# I2CHubMultiplexer.net
KiCad netlist of a schematic drawn in EAGLE
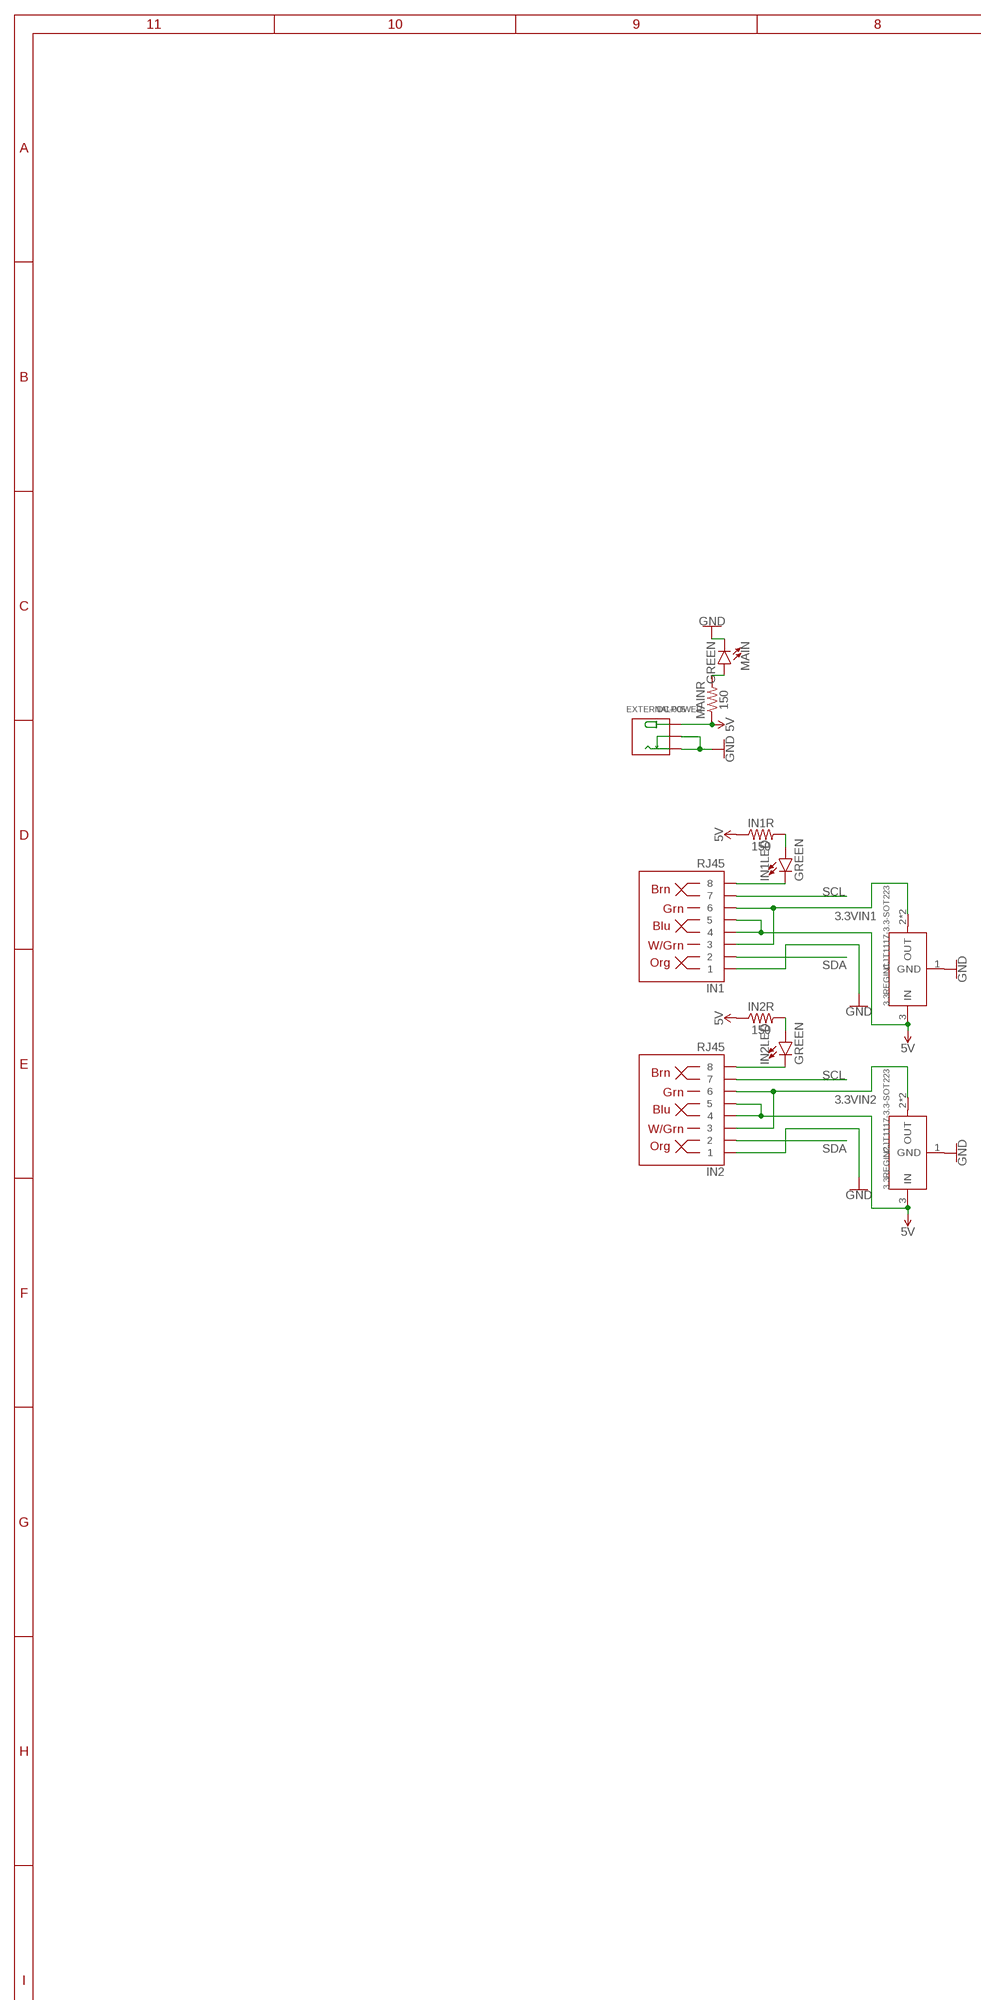
[diagram p0: schematic, sheet 1, part 1 of 2]
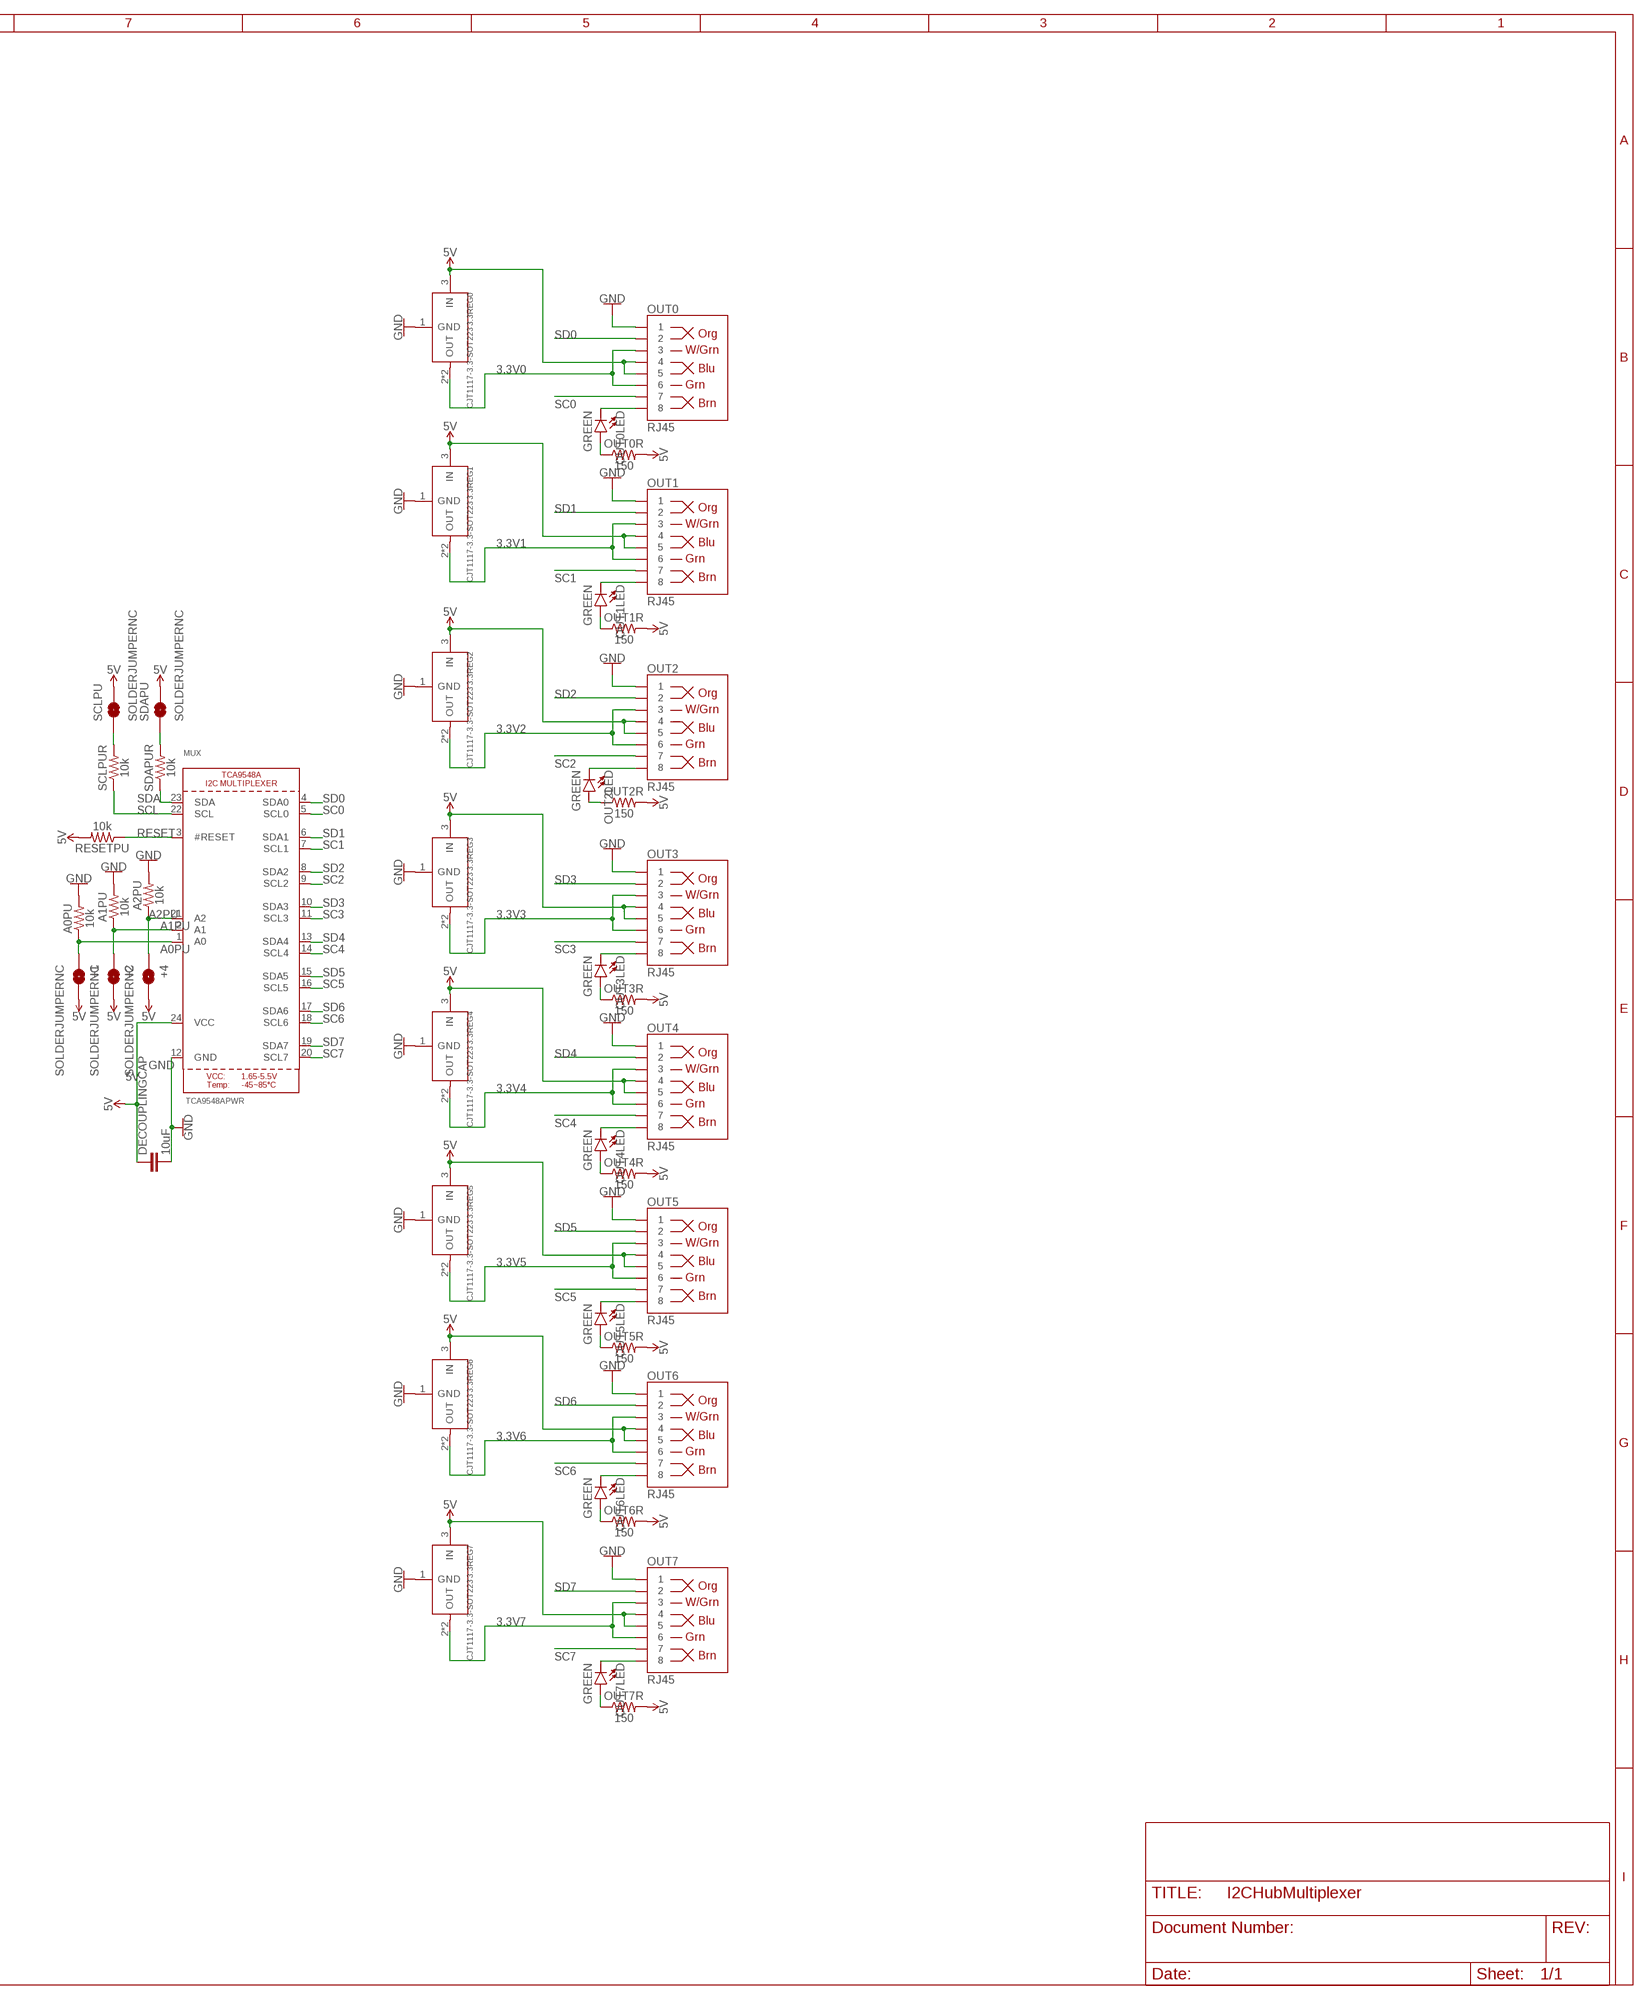
[diagram p1: schematic, sheet 1, part 2 of 2]

(export (version "E")
  (design (tool "Eeschema 10.0.6"))
  (components
    (comp (ref "+1")
      (value "SOLDERJUMPERNC")
      (footprint "eagle-import:SJ_2S")
      (libsource (lib "eagle-import") (part "SOLDERJUMPERNC"))
    )
    (comp (ref "+2")
      (value "SOLDERJUMPERNC")
      (footprint "eagle-import:SJ_2S")
      (libsource (lib "eagle-import") (part "SOLDERJUMPERNC"))
    )
    (comp (ref "+4")
      (value "SOLDERJUMPERNC")
      (footprint "eagle-import:SJ_2S")
      (libsource (lib "eagle-import") (part "SOLDERJUMPERNC"))
    )
    (comp (ref "3.3REG0")
      (value "CJT1117-3.3-SOT223")
      (footprint "eagle-import:SOT-223")
      (fields (field (name "MPN") "CJT1117-3.3"))
      (libsource (lib "eagle-import") (part "PMIC-CJT1117-3.3(SOT223)"))
    )
    (comp (ref "3.3REG1")
      (value "CJT1117-3.3-SOT223")
      (footprint "eagle-import:SOT-223")
      (fields (field (name "MPN") "CJT1117-3.3"))
      (libsource (lib "eagle-import") (part "PMIC-CJT1117-3.3(SOT223)"))
    )
    (comp (ref "3.3REG2")
      (value "CJT1117-3.3-SOT223")
      (footprint "eagle-import:SOT-223")
      (fields (field (name "MPN") "CJT1117-3.3"))
      (libsource (lib "eagle-import") (part "PMIC-CJT1117-3.3(SOT223)"))
    )
    (comp (ref "3.3REG3")
      (value "CJT1117-3.3-SOT223")
      (footprint "eagle-import:SOT-223")
      (fields (field (name "MPN") "CJT1117-3.3"))
      (libsource (lib "eagle-import") (part "PMIC-CJT1117-3.3(SOT223)"))
    )
    (comp (ref "3.3REG4")
      (value "CJT1117-3.3-SOT223")
      (footprint "eagle-import:SOT-223")
      (fields (field (name "MPN") "CJT1117-3.3"))
      (libsource (lib "eagle-import") (part "PMIC-CJT1117-3.3(SOT223)"))
    )
    (comp (ref "3.3REG5")
      (value "CJT1117-3.3-SOT223")
      (footprint "eagle-import:SOT-223")
      (fields (field (name "MPN") "CJT1117-3.3"))
      (libsource (lib "eagle-import") (part "PMIC-CJT1117-3.3(SOT223)"))
    )
    (comp (ref "3.3REG6")
      (value "CJT1117-3.3-SOT223")
      (footprint "eagle-import:SOT-223")
      (fields (field (name "MPN") "CJT1117-3.3"))
      (libsource (lib "eagle-import") (part "PMIC-CJT1117-3.3(SOT223)"))
    )
    (comp (ref "3.3REG7")
      (value "CJT1117-3.3-SOT223")
      (footprint "eagle-import:SOT-223")
      (fields (field (name "MPN") "CJT1117-3.3"))
      (libsource (lib "eagle-import") (part "PMIC-CJT1117-3.3(SOT223)"))
    )
    (comp (ref "3.3REGIN1")
      (value "CJT1117-3.3-SOT223")
      (footprint "eagle-import:SOT-223")
      (fields (field (name "MPN") "CJT1117-3.3"))
      (libsource (lib "eagle-import") (part "PMIC-CJT1117-3.3(SOT223)"))
    )
    (comp (ref "3.3REGIN2")
      (value "CJT1117-3.3-SOT223")
      (footprint "eagle-import:SOT-223")
      (fields (field (name "MPN") "CJT1117-3.3"))
      (libsource (lib "eagle-import") (part "PMIC-CJT1117-3.3(SOT223)"))
    )
    (comp (ref "A0PU")
      (value "10k")
      (footprint "eagle-import:0603")
      (libsource (lib "eagle-import") (part "10KOHM-0603-1/10W-1%"))
    )
    (comp (ref "A1PU")
      (value "10k")
      (footprint "eagle-import:0603")
      (libsource (lib "eagle-import") (part "10KOHM-0603-1/10W-1%"))
    )
    (comp (ref "A2PU")
      (value "10k")
      (footprint "eagle-import:0603")
      (libsource (lib "eagle-import") (part "10KOHM-0603-1/10W-1%"))
    )
    (comp (ref "DECOUPLINGCAP")
      (value "10uF")
      (footprint "eagle-import:0603")
      (libsource (lib "eagle-import") (part "10UF-0603-6.3V-20%"))
    )
    (comp (ref "EXTERNALPOWER")
      (value "DC-005")
      (footprint "eagle-import:DCJ3P-14.2X11.0X9.0MM")
      (libsource (lib "eagle-import") (part "CONN-POWER-JACK-2.1MM(DC-005)"))
    )
    (comp (ref "IN1")
      (value "RJ45")
      (footprint "eagle-import:RJ45-8")
      (libsource (lib "eagle-import") (part "RJ45-8"))
    )
    (comp (ref "IN1LED")
      (value "GREEN")
      (footprint "eagle-import:LED-0603")
      (libsource (lib "eagle-import") (part "LED-GREEN0603"))
    )
    (comp (ref "IN1R")
      (value "150")
      (footprint "eagle-import:0603")
      (libsource (lib "eagle-import") (part "150OHM-0603-1/10W-1%"))
    )
    (comp (ref "IN2")
      (value "RJ45")
      (footprint "eagle-import:RJ45-8")
      (libsource (lib "eagle-import") (part "RJ45-8"))
    )
    (comp (ref "IN2LED")
      (value "GREEN")
      (footprint "eagle-import:LED-0603")
      (libsource (lib "eagle-import") (part "LED-GREEN0603"))
    )
    (comp (ref "IN2R")
      (value "150")
      (footprint "eagle-import:0603")
      (libsource (lib "eagle-import") (part "150OHM-0603-1/10W-1%"))
    )
    (comp (ref "MAIN")
      (value "GREEN")
      (footprint "eagle-import:LED-0603")
      (libsource (lib "eagle-import") (part "LED-GREEN0603"))
    )
    (comp (ref "MAINR")
      (value "150")
      (footprint "eagle-import:0603")
      (libsource (lib "eagle-import") (part "150OHM-0603-1/10W-1%"))
    )
    (comp (ref "MUX")
      (value "TCA9548APWR")
      (footprint "eagle-import:TSSOP24")
      (libsource (lib "eagle-import") (part "TCA9548A"))
    )
    (comp (ref "OUT0")
      (value "RJ45")
      (footprint "eagle-import:RJ45-8")
      (libsource (lib "eagle-import") (part "RJ45-8"))
    )
    (comp (ref "OUT0LED")
      (value "GREEN")
      (footprint "eagle-import:LED-0603")
      (libsource (lib "eagle-import") (part "LED-GREEN0603"))
    )
    (comp (ref "OUT0R")
      (value "150")
      (footprint "eagle-import:0603")
      (libsource (lib "eagle-import") (part "150OHM-0603-1/10W-1%"))
    )
    (comp (ref "OUT1")
      (value "RJ45")
      (footprint "eagle-import:RJ45-8")
      (libsource (lib "eagle-import") (part "RJ45-8"))
    )
    (comp (ref "OUT1LED")
      (value "GREEN")
      (footprint "eagle-import:LED-0603")
      (libsource (lib "eagle-import") (part "LED-GREEN0603"))
    )
    (comp (ref "OUT1R")
      (value "150")
      (footprint "eagle-import:0603")
      (libsource (lib "eagle-import") (part "150OHM-0603-1/10W-1%"))
    )
    (comp (ref "OUT2")
      (value "RJ45")
      (footprint "eagle-import:RJ45-8")
      (libsource (lib "eagle-import") (part "RJ45-8"))
    )
    (comp (ref "OUT2LED")
      (value "GREEN")
      (footprint "eagle-import:LED-0603")
      (libsource (lib "eagle-import") (part "LED-GREEN0603"))
    )
    (comp (ref "OUT2R")
      (value "150")
      (footprint "eagle-import:0603")
      (libsource (lib "eagle-import") (part "150OHM-0603-1/10W-1%"))
    )
    (comp (ref "OUT3")
      (value "RJ45")
      (footprint "eagle-import:RJ45-8")
      (libsource (lib "eagle-import") (part "RJ45-8"))
    )
    (comp (ref "OUT3LED")
      (value "GREEN")
      (footprint "eagle-import:LED-0603")
      (libsource (lib "eagle-import") (part "LED-GREEN0603"))
    )
    (comp (ref "OUT3R")
      (value "150")
      (footprint "eagle-import:0603")
      (libsource (lib "eagle-import") (part "150OHM-0603-1/10W-1%"))
    )
    (comp (ref "OUT4")
      (value "RJ45")
      (footprint "eagle-import:RJ45-8")
      (libsource (lib "eagle-import") (part "RJ45-8"))
    )
    (comp (ref "OUT4LED")
      (value "GREEN")
      (footprint "eagle-import:LED-0603")
      (libsource (lib "eagle-import") (part "LED-GREEN0603"))
    )
    (comp (ref "OUT4R")
      (value "150")
      (footprint "eagle-import:0603")
      (libsource (lib "eagle-import") (part "150OHM-0603-1/10W-1%"))
    )
    (comp (ref "OUT5")
      (value "RJ45")
      (footprint "eagle-import:RJ45-8")
      (libsource (lib "eagle-import") (part "RJ45-8"))
    )
    (comp (ref "OUT5LED")
      (value "GREEN")
      (footprint "eagle-import:LED-0603")
      (libsource (lib "eagle-import") (part "LED-GREEN0603"))
    )
    (comp (ref "OUT5R")
      (value "150")
      (footprint "eagle-import:0603")
      (libsource (lib "eagle-import") (part "150OHM-0603-1/10W-1%"))
    )
    (comp (ref "OUT6")
      (value "RJ45")
      (footprint "eagle-import:RJ45-8")
      (libsource (lib "eagle-import") (part "RJ45-8"))
    )
    (comp (ref "OUT6LED")
      (value "GREEN")
      (footprint "eagle-import:LED-0603")
      (libsource (lib "eagle-import") (part "LED-GREEN0603"))
    )
    (comp (ref "OUT6R")
      (value "150")
      (footprint "eagle-import:0603")
      (libsource (lib "eagle-import") (part "150OHM-0603-1/10W-1%"))
    )
    (comp (ref "OUT7")
      (value "RJ45")
      (footprint "eagle-import:RJ45-8")
      (libsource (lib "eagle-import") (part "RJ45-8"))
    )
    (comp (ref "OUT7LED")
      (value "GREEN")
      (footprint "eagle-import:LED-0603")
      (libsource (lib "eagle-import") (part "LED-GREEN0603"))
    )
    (comp (ref "OUT7R")
      (value "150")
      (footprint "eagle-import:0603")
      (libsource (lib "eagle-import") (part "150OHM-0603-1/10W-1%"))
    )
    (comp (ref "RESETPU")
      (value "10k")
      (footprint "eagle-import:0603")
      (libsource (lib "eagle-import") (part "10KOHM-0603-1/10W-1%"))
    )
    (comp (ref "SCLPU")
      (value "SOLDERJUMPERNC")
      (footprint "eagle-import:SJ_2S")
      (libsource (lib "eagle-import") (part "SOLDERJUMPERNC"))
    )
    (comp (ref "SCLPUR")
      (value "10k")
      (footprint "eagle-import:0603")
      (libsource (lib "eagle-import") (part "10KOHM-0603-1/10W-1%"))
    )
    (comp (ref "SDAPU")
      (value "SOLDERJUMPERNC")
      (footprint "eagle-import:SJ_2S")
      (libsource (lib "eagle-import") (part "SOLDERJUMPERNC"))
    )
    (comp (ref "SDAPUR")
      (value "10k")
      (footprint "eagle-import:0603")
      (libsource (lib "eagle-import") (part "10KOHM-0603-1/10W-1%"))
    )
  )
  (nets
    (net (code "1") (name "/3.3V0") (class "Default")
      (node (ref "3.3REG0") (pin "2") (pinfunction "OUT_2") (pintype "bidirectional"))
      (node (ref "3.3REG0") (pin "TER") (pinfunction "OUT_TER") (pintype "bidirectional"))
      (node (ref "OUT0") (pin "3") (pinfunction "3_3") (pintype "bidirectional"))
      (node (ref "OUT0") (pin "6") (pinfunction "6_6") (pintype "bidirectional"))
    )
    (net (code "2") (name "/3.3V1") (class "Default")
      (node (ref "3.3REG1") (pin "2") (pinfunction "OUT_2") (pintype "bidirectional"))
      (node (ref "3.3REG1") (pin "TER") (pinfunction "OUT_TER") (pintype "bidirectional"))
      (node (ref "OUT1") (pin "3") (pinfunction "3_3") (pintype "bidirectional"))
      (node (ref "OUT1") (pin "6") (pinfunction "6_6") (pintype "bidirectional"))
    )
    (net (code "3") (name "/3.3V2") (class "Default")
      (node (ref "3.3REG2") (pin "2") (pinfunction "OUT_2") (pintype "bidirectional"))
      (node (ref "3.3REG2") (pin "TER") (pinfunction "OUT_TER") (pintype "bidirectional"))
      (node (ref "OUT2") (pin "3") (pinfunction "3_3") (pintype "bidirectional"))
      (node (ref "OUT2") (pin "6") (pinfunction "6_6") (pintype "bidirectional"))
    )
    (net (code "4") (name "/3.3V3") (class "Default")
      (node (ref "3.3REG3") (pin "2") (pinfunction "OUT_2") (pintype "bidirectional"))
      (node (ref "3.3REG3") (pin "TER") (pinfunction "OUT_TER") (pintype "bidirectional"))
      (node (ref "OUT3") (pin "3") (pinfunction "3_3") (pintype "bidirectional"))
      (node (ref "OUT3") (pin "6") (pinfunction "6_6") (pintype "bidirectional"))
    )
    (net (code "5") (name "/3.3V4") (class "Default")
      (node (ref "3.3REG4") (pin "2") (pinfunction "OUT_2") (pintype "bidirectional"))
      (node (ref "3.3REG4") (pin "TER") (pinfunction "OUT_TER") (pintype "bidirectional"))
      (node (ref "OUT4") (pin "3") (pinfunction "3_3") (pintype "bidirectional"))
      (node (ref "OUT4") (pin "6") (pinfunction "6_6") (pintype "bidirectional"))
    )
    (net (code "6") (name "/3.3V5") (class "Default")
      (node (ref "3.3REG5") (pin "2") (pinfunction "OUT_2") (pintype "bidirectional"))
      (node (ref "3.3REG5") (pin "TER") (pinfunction "OUT_TER") (pintype "bidirectional"))
      (node (ref "OUT5") (pin "3") (pinfunction "3_3") (pintype "bidirectional"))
      (node (ref "OUT5") (pin "6") (pinfunction "6_6") (pintype "bidirectional"))
    )
    (net (code "7") (name "/3.3V6") (class "Default")
      (node (ref "3.3REG6") (pin "2") (pinfunction "OUT_2") (pintype "bidirectional"))
      (node (ref "3.3REG6") (pin "TER") (pinfunction "OUT_TER") (pintype "bidirectional"))
      (node (ref "OUT6") (pin "3") (pinfunction "3_3") (pintype "bidirectional"))
      (node (ref "OUT6") (pin "6") (pinfunction "6_6") (pintype "bidirectional"))
    )
    (net (code "8") (name "/3.3V7") (class "Default")
      (node (ref "3.3REG7") (pin "2") (pinfunction "OUT_2") (pintype "bidirectional"))
      (node (ref "3.3REG7") (pin "TER") (pinfunction "OUT_TER") (pintype "bidirectional"))
      (node (ref "OUT7") (pin "3") (pinfunction "3_3") (pintype "bidirectional"))
      (node (ref "OUT7") (pin "6") (pinfunction "6_6") (pintype "bidirectional"))
    )
    (net (code "9") (name "/3.3VIN1") (class "Default")
      (node (ref "3.3REGIN1") (pin "2") (pinfunction "OUT_2") (pintype "bidirectional"))
      (node (ref "3.3REGIN1") (pin "TER") (pinfunction "OUT_TER") (pintype "bidirectional"))
      (node (ref "IN1") (pin "3") (pinfunction "3_3") (pintype "bidirectional"))
      (node (ref "IN1") (pin "6") (pinfunction "6_6") (pintype "bidirectional"))
    )
    (net (code "10") (name "/3.3VIN2") (class "Default")
      (node (ref "3.3REGIN2") (pin "2") (pinfunction "OUT_2") (pintype "bidirectional"))
      (node (ref "3.3REGIN2") (pin "TER") (pinfunction "OUT_TER") (pintype "bidirectional"))
      (node (ref "IN2") (pin "3") (pinfunction "3_3") (pintype "bidirectional"))
      (node (ref "IN2") (pin "6") (pinfunction "6_6") (pintype "bidirectional"))
    )
    (net (code "11") (name "/A0PU") (class "Default")
      (node (ref "+1") (pin "1") (pinfunction "1_1") (pintype "passive"))
      (node (ref "A0PU") (pin "1") (pinfunction "1_1") (pintype "passive"))
      (node (ref "MUX") (pin "1") (pinfunction "A0_1") (pintype "bidirectional"))
    )
    (net (code "12") (name "/A1PU") (class "Default")
      (node (ref "+2") (pin "1") (pinfunction "1_1") (pintype "passive"))
      (node (ref "A1PU") (pin "1") (pinfunction "1_1") (pintype "passive"))
      (node (ref "MUX") (pin "2") (pinfunction "A1_2") (pintype "bidirectional"))
    )
    (net (code "13") (name "/A2PU") (class "Default")
      (node (ref "+4") (pin "1") (pinfunction "1_1") (pintype "passive"))
      (node (ref "A2PU") (pin "1") (pinfunction "1_1") (pintype "passive"))
      (node (ref "MUX") (pin "21") (pinfunction "A2_21") (pintype "bidirectional"))
    )
    (net (code "14") (name "/RESET") (class "Default")
      (node (ref "MUX") (pin "3") (pinfunction "#RESET_3") (pintype "bidirectional"))
      (node (ref "RESETPU") (pin "1") (pinfunction "1_1") (pintype "passive"))
    )
    (net (code "15") (name "/SC0") (class "Default")
      (node (ref "MUX") (pin "5") (pinfunction "SCL0_5") (pintype "bidirectional"))
      (node (ref "OUT0") (pin "7") (pinfunction "7_7") (pintype "bidirectional"))
    )
    (net (code "16") (name "/SC1") (class "Default")
      (node (ref "MUX") (pin "7") (pinfunction "SCL1_7") (pintype "bidirectional"))
      (node (ref "OUT1") (pin "7") (pinfunction "7_7") (pintype "bidirectional"))
    )
    (net (code "17") (name "/SC2") (class "Default")
      (node (ref "MUX") (pin "9") (pinfunction "SCL2_9") (pintype "bidirectional"))
      (node (ref "OUT2") (pin "7") (pinfunction "7_7") (pintype "bidirectional"))
    )
    (net (code "18") (name "/SC3") (class "Default")
      (node (ref "MUX") (pin "11") (pinfunction "SCL3_11") (pintype "bidirectional"))
      (node (ref "OUT3") (pin "7") (pinfunction "7_7") (pintype "bidirectional"))
    )
    (net (code "19") (name "/SC4") (class "Default")
      (node (ref "MUX") (pin "14") (pinfunction "SCL4_14") (pintype "bidirectional"))
      (node (ref "OUT4") (pin "7") (pinfunction "7_7") (pintype "bidirectional"))
    )
    (net (code "20") (name "/SC5") (class "Default")
      (node (ref "MUX") (pin "16") (pinfunction "SCL5_16") (pintype "bidirectional"))
      (node (ref "OUT5") (pin "7") (pinfunction "7_7") (pintype "bidirectional"))
    )
    (net (code "21") (name "/SC6") (class "Default")
      (node (ref "MUX") (pin "18") (pinfunction "SCL6_18") (pintype "bidirectional"))
      (node (ref "OUT6") (pin "7") (pinfunction "7_7") (pintype "bidirectional"))
    )
    (net (code "22") (name "/SC7") (class "Default")
      (node (ref "MUX") (pin "20") (pinfunction "SCL7_20") (pintype "bidirectional"))
      (node (ref "OUT7") (pin "7") (pinfunction "7_7") (pintype "bidirectional"))
    )
    (net (code "23") (name "/SCL") (class "Default")
      (node (ref "IN1") (pin "7") (pinfunction "7_7") (pintype "bidirectional"))
      (node (ref "IN2") (pin "7") (pinfunction "7_7") (pintype "bidirectional"))
      (node (ref "MUX") (pin "22") (pinfunction "SCL_22") (pintype "bidirectional"))
      (node (ref "SCLPUR") (pin "1") (pinfunction "1_1") (pintype "passive"))
    )
    (net (code "24") (name "/SD0") (class "Default")
      (node (ref "MUX") (pin "4") (pinfunction "SDA0_4") (pintype "bidirectional"))
      (node (ref "OUT0") (pin "2") (pinfunction "2_2") (pintype "bidirectional"))
    )
    (net (code "25") (name "/SD1") (class "Default")
      (node (ref "MUX") (pin "6") (pinfunction "SDA1_6") (pintype "bidirectional"))
      (node (ref "OUT1") (pin "2") (pinfunction "2_2") (pintype "bidirectional"))
    )
    (net (code "26") (name "/SD2") (class "Default")
      (node (ref "MUX") (pin "8") (pinfunction "SDA2_8") (pintype "bidirectional"))
      (node (ref "OUT2") (pin "2") (pinfunction "2_2") (pintype "bidirectional"))
    )
    (net (code "27") (name "/SD3") (class "Default")
      (node (ref "MUX") (pin "10") (pinfunction "SDA3_10") (pintype "bidirectional"))
      (node (ref "OUT3") (pin "2") (pinfunction "2_2") (pintype "bidirectional"))
    )
    (net (code "28") (name "/SD4") (class "Default")
      (node (ref "MUX") (pin "13") (pinfunction "SDA4_13") (pintype "bidirectional"))
      (node (ref "OUT4") (pin "2") (pinfunction "2_2") (pintype "bidirectional"))
    )
    (net (code "29") (name "/SD5") (class "Default")
      (node (ref "MUX") (pin "15") (pinfunction "SDA5_15") (pintype "bidirectional"))
      (node (ref "OUT5") (pin "2") (pinfunction "2_2") (pintype "bidirectional"))
    )
    (net (code "30") (name "/SD6") (class "Default")
      (node (ref "MUX") (pin "17") (pinfunction "SDA6_17") (pintype "bidirectional"))
      (node (ref "OUT6") (pin "2") (pinfunction "2_2") (pintype "bidirectional"))
    )
    (net (code "31") (name "/SD7") (class "Default")
      (node (ref "MUX") (pin "19") (pinfunction "SDA7_19") (pintype "bidirectional"))
      (node (ref "OUT7") (pin "2") (pinfunction "2_2") (pintype "bidirectional"))
    )
    (net (code "32") (name "/SDA") (class "Default")
      (node (ref "IN1") (pin "2") (pinfunction "2_2") (pintype "bidirectional"))
      (node (ref "IN2") (pin "2") (pinfunction "2_2") (pintype "bidirectional"))
      (node (ref "MUX") (pin "23") (pinfunction "SDA_23") (pintype "bidirectional"))
      (node (ref "SDAPUR") (pin "1") (pinfunction "1_1") (pintype "passive"))
    )
    (net (code "33") (name "5V") (class "Default")
      (node (ref "+1") (pin "2") (pinfunction "2_2") (pintype "passive"))
      (node (ref "+2") (pin "2") (pinfunction "2_2") (pintype "passive"))
      (node (ref "+4") (pin "2") (pinfunction "2_2") (pintype "passive"))
      (node (ref "3.3REG0") (pin "3") (pinfunction "IN_3") (pintype "bidirectional"))
      (node (ref "3.3REG1") (pin "3") (pinfunction "IN_3") (pintype "bidirectional"))
      (node (ref "3.3REG2") (pin "3") (pinfunction "IN_3") (pintype "bidirectional"))
      (node (ref "3.3REG3") (pin "3") (pinfunction "IN_3") (pintype "bidirectional"))
      (node (ref "3.3REG4") (pin "3") (pinfunction "IN_3") (pintype "bidirectional"))
      (node (ref "3.3REG5") (pin "3") (pinfunction "IN_3") (pintype "bidirectional"))
      (node (ref "3.3REG6") (pin "3") (pinfunction "IN_3") (pintype "bidirectional"))
      (node (ref "3.3REG7") (pin "3") (pinfunction "IN_3") (pintype "bidirectional"))
      (node (ref "3.3REGIN1") (pin "3") (pinfunction "IN_3") (pintype "bidirectional"))
      (node (ref "3.3REGIN2") (pin "3") (pinfunction "IN_3") (pintype "bidirectional"))
      (node (ref "DECOUPLINGCAP") (pin "1") (pinfunction "1_1") (pintype "passive"))
      (node (ref "EXTERNALPOWER") (pin "+") (pinfunction "+_+") (pintype "bidirectional"))
      (node (ref "IN1") (pin "4") (pinfunction "4_4") (pintype "bidirectional"))
      (node (ref "IN1") (pin "5") (pinfunction "5_5") (pintype "bidirectional"))
      (node (ref "IN1R") (pin "1") (pinfunction "1_1") (pintype "passive"))
      (node (ref "IN2") (pin "4") (pinfunction "4_4") (pintype "bidirectional"))
      (node (ref "IN2") (pin "5") (pinfunction "5_5") (pintype "bidirectional"))
      (node (ref "IN2R") (pin "1") (pinfunction "1_1") (pintype "passive"))
      (node (ref "MAINR") (pin "1") (pinfunction "1_1") (pintype "passive"))
      (node (ref "MUX") (pin "24") (pinfunction "VCC_24") (pintype "bidirectional"))
      (node (ref "OUT0") (pin "4") (pinfunction "4_4") (pintype "bidirectional"))
      (node (ref "OUT0") (pin "5") (pinfunction "5_5") (pintype "bidirectional"))
      (node (ref "OUT0R") (pin "2") (pinfunction "2_2") (pintype "passive"))
      (node (ref "OUT1") (pin "4") (pinfunction "4_4") (pintype "bidirectional"))
      (node (ref "OUT1") (pin "5") (pinfunction "5_5") (pintype "bidirectional"))
      (node (ref "OUT1R") (pin "2") (pinfunction "2_2") (pintype "passive"))
      (node (ref "OUT2") (pin "4") (pinfunction "4_4") (pintype "bidirectional"))
      (node (ref "OUT2") (pin "5") (pinfunction "5_5") (pintype "bidirectional"))
      (node (ref "OUT2R") (pin "2") (pinfunction "2_2") (pintype "passive"))
      (node (ref "OUT3") (pin "4") (pinfunction "4_4") (pintype "bidirectional"))
      (node (ref "OUT3") (pin "5") (pinfunction "5_5") (pintype "bidirectional"))
      (node (ref "OUT3R") (pin "2") (pinfunction "2_2") (pintype "passive"))
      (node (ref "OUT4") (pin "4") (pinfunction "4_4") (pintype "bidirectional"))
      (node (ref "OUT4") (pin "5") (pinfunction "5_5") (pintype "bidirectional"))
      (node (ref "OUT4R") (pin "2") (pinfunction "2_2") (pintype "passive"))
      (node (ref "OUT5") (pin "4") (pinfunction "4_4") (pintype "bidirectional"))
      (node (ref "OUT5") (pin "5") (pinfunction "5_5") (pintype "bidirectional"))
      (node (ref "OUT5R") (pin "2") (pinfunction "2_2") (pintype "passive"))
      (node (ref "OUT6") (pin "4") (pinfunction "4_4") (pintype "bidirectional"))
      (node (ref "OUT6") (pin "5") (pinfunction "5_5") (pintype "bidirectional"))
      (node (ref "OUT6R") (pin "2") (pinfunction "2_2") (pintype "passive"))
      (node (ref "OUT7") (pin "4") (pinfunction "4_4") (pintype "bidirectional"))
      (node (ref "OUT7") (pin "5") (pinfunction "5_5") (pintype "bidirectional"))
      (node (ref "OUT7R") (pin "2") (pinfunction "2_2") (pintype "passive"))
      (node (ref "RESETPU") (pin "2") (pinfunction "2_2") (pintype "passive"))
      (node (ref "SCLPU") (pin "2") (pinfunction "2_2") (pintype "passive"))
      (node (ref "SDAPU") (pin "2") (pinfunction "2_2") (pintype "passive"))
    )
    (net (code "34") (name "GND") (class "Default")
      (node (ref "3.3REG0") (pin "1") (pinfunction "GND_1") (pintype "bidirectional"))
      (node (ref "3.3REG1") (pin "1") (pinfunction "GND_1") (pintype "bidirectional"))
      (node (ref "3.3REG2") (pin "1") (pinfunction "GND_1") (pintype "bidirectional"))
      (node (ref "3.3REG3") (pin "1") (pinfunction "GND_1") (pintype "bidirectional"))
      (node (ref "3.3REG4") (pin "1") (pinfunction "GND_1") (pintype "bidirectional"))
      (node (ref "3.3REG5") (pin "1") (pinfunction "GND_1") (pintype "bidirectional"))
      (node (ref "3.3REG6") (pin "1") (pinfunction "GND_1") (pintype "bidirectional"))
      (node (ref "3.3REG7") (pin "1") (pinfunction "GND_1") (pintype "bidirectional"))
      (node (ref "3.3REGIN1") (pin "1") (pinfunction "GND_1") (pintype "bidirectional"))
      (node (ref "3.3REGIN2") (pin "1") (pinfunction "GND_1") (pintype "bidirectional"))
      (node (ref "A0PU") (pin "2") (pinfunction "2_2") (pintype "passive"))
      (node (ref "A1PU") (pin "2") (pinfunction "2_2") (pintype "passive"))
      (node (ref "A2PU") (pin "2") (pinfunction "2_2") (pintype "passive"))
      (node (ref "DECOUPLINGCAP") (pin "2") (pinfunction "2_2") (pintype "passive"))
      (node (ref "EXTERNALPOWER") (pin "-1") (pinfunction "-_-1") (pintype "bidirectional"))
      (node (ref "EXTERNALPOWER") (pin "-2") (pinfunction "CDN_-2") (pintype "bidirectional"))
      (node (ref "IN1") (pin "1") (pinfunction "1_1") (pintype "bidirectional"))
      (node (ref "IN2") (pin "1") (pinfunction "1_1") (pintype "bidirectional"))
      (node (ref "MAIN") (pin "C") (pinfunction "C_C") (pintype "passive"))
      (node (ref "MUX") (pin "12") (pinfunction "GND_12") (pintype "bidirectional"))
      (node (ref "OUT0") (pin "1") (pinfunction "1_1") (pintype "bidirectional"))
      (node (ref "OUT1") (pin "1") (pinfunction "1_1") (pintype "bidirectional"))
      (node (ref "OUT2") (pin "1") (pinfunction "1_1") (pintype "bidirectional"))
      (node (ref "OUT3") (pin "1") (pinfunction "1_1") (pintype "bidirectional"))
      (node (ref "OUT4") (pin "1") (pinfunction "1_1") (pintype "bidirectional"))
      (node (ref "OUT5") (pin "1") (pinfunction "1_1") (pintype "bidirectional"))
      (node (ref "OUT6") (pin "1") (pinfunction "1_1") (pintype "bidirectional"))
      (node (ref "OUT7") (pin "1") (pinfunction "1_1") (pintype "bidirectional"))
    )
    (net (code "35") (name "Net-(IN1-Pad8)") (class "Default")
      (node (ref "IN1") (pin "8") (pinfunction "8_8") (pintype "bidirectional"))
      (node (ref "IN1LED") (pin "C") (pinfunction "C_C") (pintype "passive"))
    )
    (net (code "36") (name "Net-(IN1LED-PadA)") (class "Default")
      (node (ref "IN1LED") (pin "A") (pinfunction "A_A") (pintype "passive"))
      (node (ref "IN1R") (pin "2") (pinfunction "2_2") (pintype "passive"))
    )
    (net (code "37") (name "Net-(IN2-Pad8)") (class "Default")
      (node (ref "IN2") (pin "8") (pinfunction "8_8") (pintype "bidirectional"))
      (node (ref "IN2LED") (pin "C") (pinfunction "C_C") (pintype "passive"))
    )
    (net (code "38") (name "Net-(IN2LED-PadA)") (class "Default")
      (node (ref "IN2LED") (pin "A") (pinfunction "A_A") (pintype "passive"))
      (node (ref "IN2R") (pin "2") (pinfunction "2_2") (pintype "passive"))
    )
    (net (code "39") (name "Net-(MAIN-PadA)") (class "Default")
      (node (ref "MAIN") (pin "A") (pinfunction "A_A") (pintype "passive"))
      (node (ref "MAINR") (pin "2") (pinfunction "2_2") (pintype "passive"))
    )
    (net (code "40") (name "Net-(OUT0-Pad8)") (class "Default")
      (node (ref "OUT0") (pin "8") (pinfunction "8_8") (pintype "bidirectional"))
      (node (ref "OUT0LED") (pin "C") (pinfunction "C_C") (pintype "passive"))
    )
    (net (code "41") (name "Net-(OUT0LED-PadA)") (class "Default")
      (node (ref "OUT0LED") (pin "A") (pinfunction "A_A") (pintype "passive"))
      (node (ref "OUT0R") (pin "1") (pinfunction "1_1") (pintype "passive"))
    )
    (net (code "42") (name "Net-(OUT1-Pad8)") (class "Default")
      (node (ref "OUT1") (pin "8") (pinfunction "8_8") (pintype "bidirectional"))
      (node (ref "OUT1LED") (pin "C") (pinfunction "C_C") (pintype "passive"))
    )
    (net (code "43") (name "Net-(OUT1LED-PadA)") (class "Default")
      (node (ref "OUT1LED") (pin "A") (pinfunction "A_A") (pintype "passive"))
      (node (ref "OUT1R") (pin "1") (pinfunction "1_1") (pintype "passive"))
    )
    (net (code "44") (name "Net-(OUT2-Pad8)") (class "Default")
      (node (ref "OUT2") (pin "8") (pinfunction "8_8") (pintype "bidirectional"))
      (node (ref "OUT2LED") (pin "C") (pinfunction "C_C") (pintype "passive"))
    )
    (net (code "45") (name "Net-(OUT2LED-PadA)") (class "Default")
      (node (ref "OUT2LED") (pin "A") (pinfunction "A_A") (pintype "passive"))
      (node (ref "OUT2R") (pin "1") (pinfunction "1_1") (pintype "passive"))
    )
    (net (code "46") (name "Net-(OUT3-Pad8)") (class "Default")
      (node (ref "OUT3") (pin "8") (pinfunction "8_8") (pintype "bidirectional"))
      (node (ref "OUT3LED") (pin "C") (pinfunction "C_C") (pintype "passive"))
    )
    (net (code "47") (name "Net-(OUT3LED-PadA)") (class "Default")
      (node (ref "OUT3LED") (pin "A") (pinfunction "A_A") (pintype "passive"))
      (node (ref "OUT3R") (pin "1") (pinfunction "1_1") (pintype "passive"))
    )
    (net (code "48") (name "Net-(OUT4-Pad8)") (class "Default")
      (node (ref "OUT4") (pin "8") (pinfunction "8_8") (pintype "bidirectional"))
      (node (ref "OUT4LED") (pin "C") (pinfunction "C_C") (pintype "passive"))
    )
    (net (code "49") (name "Net-(OUT4LED-PadA)") (class "Default")
      (node (ref "OUT4LED") (pin "A") (pinfunction "A_A") (pintype "passive"))
      (node (ref "OUT4R") (pin "1") (pinfunction "1_1") (pintype "passive"))
    )
    (net (code "50") (name "Net-(OUT5-Pad8)") (class "Default")
      (node (ref "OUT5") (pin "8") (pinfunction "8_8") (pintype "bidirectional"))
      (node (ref "OUT5LED") (pin "C") (pinfunction "C_C") (pintype "passive"))
    )
    (net (code "51") (name "Net-(OUT5LED-PadA)") (class "Default")
      (node (ref "OUT5LED") (pin "A") (pinfunction "A_A") (pintype "passive"))
      (node (ref "OUT5R") (pin "1") (pinfunction "1_1") (pintype "passive"))
    )
    (net (code "52") (name "Net-(OUT6-Pad8)") (class "Default")
      (node (ref "OUT6") (pin "8") (pinfunction "8_8") (pintype "bidirectional"))
      (node (ref "OUT6LED") (pin "C") (pinfunction "C_C") (pintype "passive"))
    )
    (net (code "53") (name "Net-(OUT6LED-PadA)") (class "Default")
      (node (ref "OUT6LED") (pin "A") (pinfunction "A_A") (pintype "passive"))
      (node (ref "OUT6R") (pin "1") (pinfunction "1_1") (pintype "passive"))
    )
    (net (code "54") (name "Net-(OUT7-Pad8)") (class "Default")
      (node (ref "OUT7") (pin "8") (pinfunction "8_8") (pintype "bidirectional"))
      (node (ref "OUT7LED") (pin "C") (pinfunction "C_C") (pintype "passive"))
    )
    (net (code "55") (name "Net-(OUT7LED-PadA)") (class "Default")
      (node (ref "OUT7LED") (pin "A") (pinfunction "A_A") (pintype "passive"))
      (node (ref "OUT7R") (pin "1") (pinfunction "1_1") (pintype "passive"))
    )
    (net (code "56") (name "Net-(SCLPU-Pad1)") (class "Default")
      (node (ref "SCLPU") (pin "1") (pinfunction "1_1") (pintype "passive"))
      (node (ref "SCLPUR") (pin "2") (pinfunction "2_2") (pintype "passive"))
    )
    (net (code "57") (name "Net-(SDAPU-Pad1)") (class "Default")
      (node (ref "SDAPU") (pin "1") (pinfunction "1_1") (pintype "passive"))
      (node (ref "SDAPUR") (pin "2") (pinfunction "2_2") (pintype "passive"))
    )
  )
)
